# Processor.net
KiCad netlist of a schematic drawn in Altium Designer
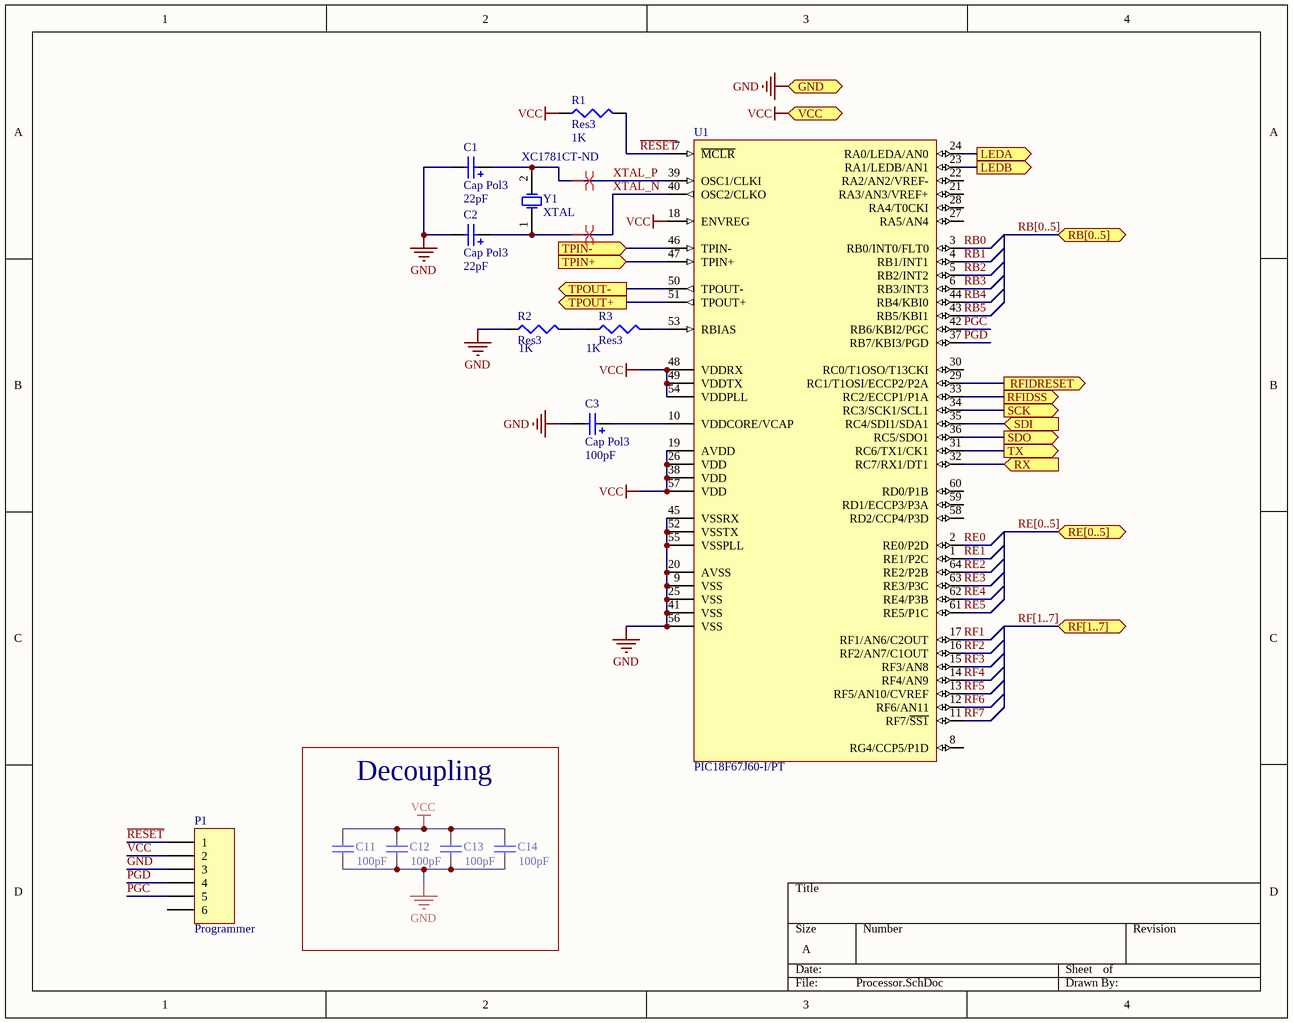
[diagram p0: Processor.SchDoc]

(export (version "E")
  (design (tool "Eeschema 10.0.6"))
  (components
    (comp (ref "C1")
      (value "Cap Pol3")
      (footprint "C0805")
      (description "Polarized Capacitor (Surface Mount)")
      (fields (field (name "ALTIUM_VALUE") "22pF") (field (name "PUBLISHER") "Altium Limited"))
      (libsource (lib "Miscellaneous Devices") (part "Cap Pol3"))
    )
    (comp (ref "C2")
      (value "Cap Pol3")
      (footprint "C0805")
      (description "Polarized Capacitor (Surface Mount)")
      (fields (field (name "ALTIUM_VALUE") "22pF") (field (name "PUBLISHER") "Altium Limited"))
      (libsource (lib "Miscellaneous Devices") (part "Cap Pol3"))
    )
    (comp (ref "C3")
      (value "Cap Pol3")
      (footprint "C0805")
      (description "Polarized Capacitor (Surface Mount)")
      (fields (field (name "ALTIUM_VALUE") "100pF") (field (name "PUBLISHER") "Altium Limited"))
      (libsource (lib "Miscellaneous Devices") (part "Cap Pol3"))
    )
    (comp (ref "C11")
      (value "100pF")
      (footprint "1608[0603]")
      (description "Capacitor (Semiconductor SIM Model)")
      (fields (field (name "Comment") "Decoupling") (field (name "PUBLISHER") "Altium Limited"))
      (libsource (lib "Miscellaneous Devices") (part "Cap Semi"))
    )
    (comp (ref "C12")
      (value "100pF")
      (footprint "1608[0603]")
      (description "Capacitor (Semiconductor SIM Model)")
      (fields (field (name "Comment") "Decoupling") (field (name "PUBLISHER") "Altium Limited"))
      (libsource (lib "Miscellaneous Devices") (part "Cap Semi"))
    )
    (comp (ref "C13")
      (value "100pF")
      (footprint "1608[0603]")
      (description "Capacitor (Semiconductor SIM Model)")
      (fields (field (name "Comment") "Decoupling") (field (name "PUBLISHER") "Altium Limited"))
      (libsource (lib "Miscellaneous Devices") (part "Cap Semi"))
    )
    (comp (ref "C14")
      (value "100pF")
      (footprint "1608[0603]")
      (description "Capacitor (Semiconductor SIM Model)")
      (fields (field (name "Comment") "Decoupling") (field (name "PUBLISHER") "Altium Limited"))
      (libsource (lib "Miscellaneous Devices") (part "Cap Semi"))
    )
    (comp (ref "P1")
      (value "Programmer")
      (footprint "HDR1X6")
      (description "Header, 6-Pin")
      (fields (field (name "PUBLISHER") "Altium Limited"))
      (libsource (lib "Miscellaneous Connectors") (part "Header 6"))
    )
    (comp (ref "R1")
      (value "Res3")
      (footprint "J1-0603")
      (description "Resistor")
      (fields (field (name "ALTIUM_VALUE") "1K") (field (name "PUBLISHER") "Altium Limited"))
      (libsource (lib "Miscellaneous Devices") (part "Res3"))
    )
    (comp (ref "R2")
      (value "Res3")
      (footprint "J1-0603")
      (description "Resistor")
      (fields (field (name "ALTIUM_VALUE") "1K") (field (name "PUBLISHER") "Altium Limited"))
      (libsource (lib "Miscellaneous Devices") (part "Res3"))
    )
    (comp (ref "R3")
      (value "Res3")
      (footprint "J1-0603")
      (description "Resistor")
      (fields (field (name "ALTIUM_VALUE") "1K") (field (name "PUBLISHER") "Altium Limited"))
      (libsource (lib "Miscellaneous Devices") (part "Res3"))
    )
    (comp (ref "U1")
      (value "PIC18F67J60-I/PT")
      (footprint "TQFP-PT64_N")
      (fields (field (name "PUBLISHER") "Altium Limited"))
      (libsource (lib "Microchip Microcontroller 8-Bit PIC18") (part "PIC18F67J60-I/PT"))
    )
    (comp (ref "Y1")
      (value "XTAL")
      (footprint "CSM-3X")
      (description "Crystal Oscillator")
      (fields
        (field (name "SUPPLIER PART NUMBER 1") "XC1781CT-ND")
        (field (name "PUBLISHER") "Altium Limited")
      )
      (libsource (lib "Miscellaneous Devices") (part "XTAL"))
    )
  )
  (nets
    (net (code "1") (name "/LEDA") (class "Default")
      (node (ref "U1") (pin "24") (pinfunction "RA0/LEDA/AN0_24") (pintype "bidirectional"))
    )
    (net (code "2") (name "/LEDB") (class "Default")
      (node (ref "U1") (pin "23") (pinfunction "RA1/LEDB/AN1_23") (pintype "bidirectional"))
    )
    (net (code "3") (name "/PGC") (class "Default")
      (node (ref "P1") (pin "5") (pinfunction "5_5") (pintype "passive"))
      (node (ref "U1") (pin "42") (pinfunction "RB6/KBI2/PGC_42") (pintype "bidirectional"))
    )
    (net (code "4") (name "/PGD") (class "Default")
      (node (ref "P1") (pin "4") (pinfunction "4_4") (pintype "passive"))
      (node (ref "U1") (pin "37") (pinfunction "RB7/KBI3/PGD_37") (pintype "bidirectional"))
    )
    (net (code "5") (name "/RB0") (class "Default")
      (node (ref "U1") (pin "3") (pinfunction "RB0/INT0/FLT0_3") (pintype "bidirectional"))
    )
    (net (code "6") (name "/RB1") (class "Default")
      (node (ref "U1") (pin "4") (pinfunction "RB1/INT1_4") (pintype "bidirectional"))
    )
    (net (code "7") (name "/RB2") (class "Default")
      (node (ref "U1") (pin "5") (pinfunction "RB2/INT2_5") (pintype "bidirectional"))
    )
    (net (code "8") (name "/RB3") (class "Default")
      (node (ref "U1") (pin "6") (pinfunction "RB3/INT3_6") (pintype "bidirectional"))
    )
    (net (code "9") (name "/RB4") (class "Default")
      (node (ref "U1") (pin "44") (pinfunction "RB4/KBI0_44") (pintype "bidirectional"))
    )
    (net (code "10") (name "/RB5") (class "Default")
      (node (ref "U1") (pin "43") (pinfunction "RB5/KBI1_43") (pintype "bidirectional"))
    )
    (net (code "12") (name "/RE0") (class "Default")
      (node (ref "U1") (pin "2") (pinfunction "RE0/P2D_2") (pintype "bidirectional"))
    )
    (net (code "13") (name "/RE1") (class "Default")
      (node (ref "U1") (pin "1") (pinfunction "RE1/P2C_1") (pintype "bidirectional"))
    )
    (net (code "14") (name "/RE2") (class "Default")
      (node (ref "U1") (pin "64") (pinfunction "RE2/P2B_64") (pintype "bidirectional"))
    )
    (net (code "15") (name "/RE3") (class "Default")
      (node (ref "U1") (pin "63") (pinfunction "RE3/P3C_63") (pintype "bidirectional"))
    )
    (net (code "16") (name "/RE4") (class "Default")
      (node (ref "U1") (pin "62") (pinfunction "RE4/P3B_62") (pintype "bidirectional"))
    )
    (net (code "17") (name "/RE5") (class "Default")
      (node (ref "U1") (pin "61") (pinfunction "RE5/P1C_61") (pintype "bidirectional"))
    )
    (net (code "19") (name "/RF1") (class "Default")
      (node (ref "U1") (pin "17") (pinfunction "RF1/AN6/C2OUT_17") (pintype "bidirectional"))
    )
    (net (code "20") (name "/RF2") (class "Default")
      (node (ref "U1") (pin "16") (pinfunction "RF2/AN7/C1OUT_16") (pintype "bidirectional"))
    )
    (net (code "21") (name "/RF3") (class "Default")
      (node (ref "U1") (pin "15") (pinfunction "RF3/AN8_15") (pintype "bidirectional"))
    )
    (net (code "22") (name "/RF4") (class "Default")
      (node (ref "U1") (pin "14") (pinfunction "RF4/AN9_14") (pintype "bidirectional"))
    )
    (net (code "23") (name "/RF5") (class "Default")
      (node (ref "U1") (pin "13") (pinfunction "RF5/AN10/CVREF_13") (pintype "bidirectional"))
    )
    (net (code "24") (name "/RF6") (class "Default")
      (node (ref "U1") (pin "12") (pinfunction "RF6/AN11_12") (pintype "bidirectional"))
    )
    (net (code "25") (name "/RF7") (class "Default")
      (node (ref "U1") (pin "11") (pinfunction "RF7/~{SS1}_11") (pintype "bidirectional"))
    )
    (net (code "26") (name "/RFIDRESET") (class "Default")
      (node (ref "U1") (pin "29") (pinfunction "RC1/T1OSI/ECCP2/P2A_29") (pintype "bidirectional"))
    )
    (net (code "27") (name "/RFIDSS") (class "Default")
      (node (ref "U1") (pin "33") (pinfunction "RC2/ECCP1/P1A_33") (pintype "bidirectional"))
    )
    (net (code "29") (name "/RX") (class "Default")
      (node (ref "U1") (pin "32") (pinfunction "RC7/RX1/DT1_32") (pintype "bidirectional"))
    )
    (net (code "30") (name "/SCK") (class "Default")
      (node (ref "U1") (pin "34") (pinfunction "RC3/SCK1/SCL1_34") (pintype "bidirectional"))
    )
    (net (code "31") (name "/SDI") (class "Default")
      (node (ref "U1") (pin "35") (pinfunction "RC4/SDI1/SDA1_35") (pintype "bidirectional"))
    )
    (net (code "32") (name "/SDO") (class "Default")
      (node (ref "U1") (pin "36") (pinfunction "RC5/SDO1_36") (pintype "bidirectional"))
    )
    (net (code "33") (name "/TPIN+") (class "Default")
      (node (ref "U1") (pin "47") (pinfunction "TPIN+_47") (pintype "input"))
    )
    (net (code "34") (name "/TPIN-") (class "Default")
      (node (ref "U1") (pin "46") (pinfunction "TPIN-_46") (pintype "input"))
    )
    (net (code "35") (name "/TPOUT+") (class "Default")
      (node (ref "U1") (pin "51") (pinfunction "TPOUT+_51") (pintype "output"))
    )
    (net (code "36") (name "/TPOUT-") (class "Default")
      (node (ref "U1") (pin "50") (pinfunction "TPOUT-_50") (pintype "output"))
    )
    (net (code "37") (name "/TX") (class "Default")
      (node (ref "U1") (pin "31") (pinfunction "RC6/TX1/CK1_31") (pintype "bidirectional"))
    )
    (net (code "38") (name "/XTAL_N") (class "Default")
      (node (ref "C2") (pin "1") (pinfunction "1_1") (pintype "passive"))
      (node (ref "U1") (pin "40") (pinfunction "OSC2/CLKO_40") (pintype "output"))
      (node (ref "Y1") (pin "1") (pinfunction "OSC1_1") (pintype "passive"))
    )
    (net (code "39") (name "/XTAL_P") (class "Default")
      (node (ref "C1") (pin "1") (pinfunction "1_1") (pintype "passive"))
      (node (ref "U1") (pin "39") (pinfunction "OSC1/CLKI_39") (pintype "input"))
      (node (ref "Y1") (pin "2") (pinfunction "OSC2_2") (pintype "passive"))
    )
    (net (code "40") (name "/~{RESET}") (class "Default")
      (node (ref "P1") (pin "1") (pinfunction "1_1") (pintype "passive"))
      (node (ref "R1") (pin "2") (pinfunction "2_2") (pintype "passive"))
      (node (ref "U1") (pin "7") (pinfunction "~{MCLR}_7") (pintype "input"))
    )
    (net (code "41") (name "GND") (class "Default")
      (node (ref "C1") (pin "2") (pinfunction "2_2") (pintype "passive"))
      (node (ref "C11") (pin "2") (pinfunction "2_2") (pintype "passive"))
      (node (ref "C12") (pin "2") (pinfunction "2_2") (pintype "passive"))
      (node (ref "C13") (pin "2") (pinfunction "2_2") (pintype "passive"))
      (node (ref "C14") (pin "2") (pinfunction "2_2") (pintype "passive"))
      (node (ref "C2") (pin "2") (pinfunction "2_2") (pintype "passive"))
      (node (ref "C3") (pin "2") (pinfunction "2_2") (pintype "passive"))
      (node (ref "P1") (pin "3") (pinfunction "3_3") (pintype "passive"))
      (node (ref "R2") (pin "1") (pinfunction "1_1") (pintype "passive"))
      (node (ref "U1") (pin "20") (pinfunction "AVSS_20") (pintype "power_in"))
      (node (ref "U1") (pin "25") (pinfunction "VSS_25") (pintype "power_in"))
      (node (ref "U1") (pin "41") (pinfunction "VSS_41") (pintype "power_in"))
      (node (ref "U1") (pin "45") (pinfunction "VSSRX_45") (pintype "power_in"))
      (node (ref "U1") (pin "52") (pinfunction "VSSTX_52") (pintype "power_in"))
      (node (ref "U1") (pin "55") (pinfunction "VSSPLL_55") (pintype "power_in"))
      (node (ref "U1") (pin "56") (pinfunction "VSS_56") (pintype "power_in"))
      (node (ref "U1") (pin "9") (pinfunction "VSS_9") (pintype "power_in"))
    )
    (net (code "42") (name "Net-(R2-Pad2)") (class "Default")
      (node (ref "R2") (pin "2") (pinfunction "2_2") (pintype "passive"))
      (node (ref "R3") (pin "1") (pinfunction "1_1") (pintype "passive"))
    )
    (net (code "43") (name "Net-(U1-RBIAS)") (class "Default")
      (node (ref "R3") (pin "2") (pinfunction "2_2") (pintype "passive"))
      (node (ref "U1") (pin "53") (pinfunction "RBIAS_53") (pintype "input"))
    )
    (net (code "44") (name "Net-(U1-VDDCORE{slash}VCAP)") (class "Default")
      (node (ref "C3") (pin "1") (pinfunction "1_1") (pintype "passive"))
      (node (ref "U1") (pin "10") (pinfunction "VDDCORE/VCAP_10") (pintype "power_in"))
    )
    (net (code "45") (name "VCC") (class "Default")
      (node (ref "C11") (pin "1") (pinfunction "1_1") (pintype "passive"))
      (node (ref "C12") (pin "1") (pinfunction "1_1") (pintype "passive"))
      (node (ref "C13") (pin "1") (pinfunction "1_1") (pintype "passive"))
      (node (ref "C14") (pin "1") (pinfunction "1_1") (pintype "passive"))
      (node (ref "P1") (pin "2") (pinfunction "2_2") (pintype "passive"))
      (node (ref "R1") (pin "1") (pinfunction "1_1") (pintype "passive"))
      (node (ref "U1") (pin "18") (pinfunction "ENVREG_18") (pintype "input"))
      (node (ref "U1") (pin "19") (pinfunction "AVDD_19") (pintype "power_in"))
      (node (ref "U1") (pin "26") (pinfunction "VDD_26") (pintype "power_in"))
      (node (ref "U1") (pin "38") (pinfunction "VDD_38") (pintype "power_in"))
      (node (ref "U1") (pin "48") (pinfunction "VDDRX_48") (pintype "power_in"))
      (node (ref "U1") (pin "49") (pinfunction "VDDTX_49") (pintype "power_in"))
      (node (ref "U1") (pin "54") (pinfunction "VDDPLL_54") (pintype "power_in"))
      (node (ref "U1") (pin "57") (pinfunction "VDD_57") (pintype "power_in"))
    )
    (net (code "46") (name "unconnected-(P1-Pad6)") (class "Default")
      (node (ref "P1") (pin "6") (pinfunction "6_6") (pintype "passive"))
    )
    (net (code "47") (name "unconnected-(U1-RA2{slash}AN2{slash}VREF--Pad22)") (class "Default")
      (node (ref "U1") (pin "22") (pinfunction "RA2/AN2/VREF-_22") (pintype "bidirectional"))
    )
    (net (code "48") (name "unconnected-(U1-RA3{slash}AN3{slash}VREF+-Pad21)") (class "Default")
      (node (ref "U1") (pin "21") (pinfunction "RA3/AN3/VREF+_21") (pintype "bidirectional"))
    )
    (net (code "49") (name "unconnected-(U1-RA4{slash}T0CKI-Pad28)") (class "Default")
      (node (ref "U1") (pin "28") (pinfunction "RA4/T0CKI_28") (pintype "bidirectional"))
    )
    (net (code "50") (name "unconnected-(U1-RA5{slash}AN4-Pad27)") (class "Default")
      (node (ref "U1") (pin "27") (pinfunction "RA5/AN4_27") (pintype "bidirectional"))
    )
    (net (code "51") (name "unconnected-(U1-RC0{slash}T1OSO{slash}T13CKI-Pad30)") (class "Default")
      (node (ref "U1") (pin "30") (pinfunction "RC0/T1OSO/T13CKI_30") (pintype "bidirectional"))
    )
    (net (code "52") (name "unconnected-(U1-RD0{slash}P1B-Pad60)") (class "Default")
      (node (ref "U1") (pin "60") (pinfunction "RD0/P1B_60") (pintype "bidirectional"))
    )
    (net (code "53") (name "unconnected-(U1-RD1{slash}ECCP3{slash}P3A-Pad59)") (class "Default")
      (node (ref "U1") (pin "59") (pinfunction "RD1/ECCP3/P3A_59") (pintype "bidirectional"))
    )
    (net (code "54") (name "unconnected-(U1-RD2{slash}CCP4{slash}P3D-Pad58)") (class "Default")
      (node (ref "U1") (pin "58") (pinfunction "RD2/CCP4/P3D_58") (pintype "bidirectional"))
    )
    (net (code "55") (name "unconnected-(U1-RG4{slash}CCP5{slash}P1D-Pad8)") (class "Default")
      (node (ref "U1") (pin "8") (pinfunction "RG4/CCP5/P1D_8") (pintype "bidirectional"))
    )
  )
)
